# sensorTensao_rev5_5.net
KiCad netlist of a schematic drawn in EAGLE
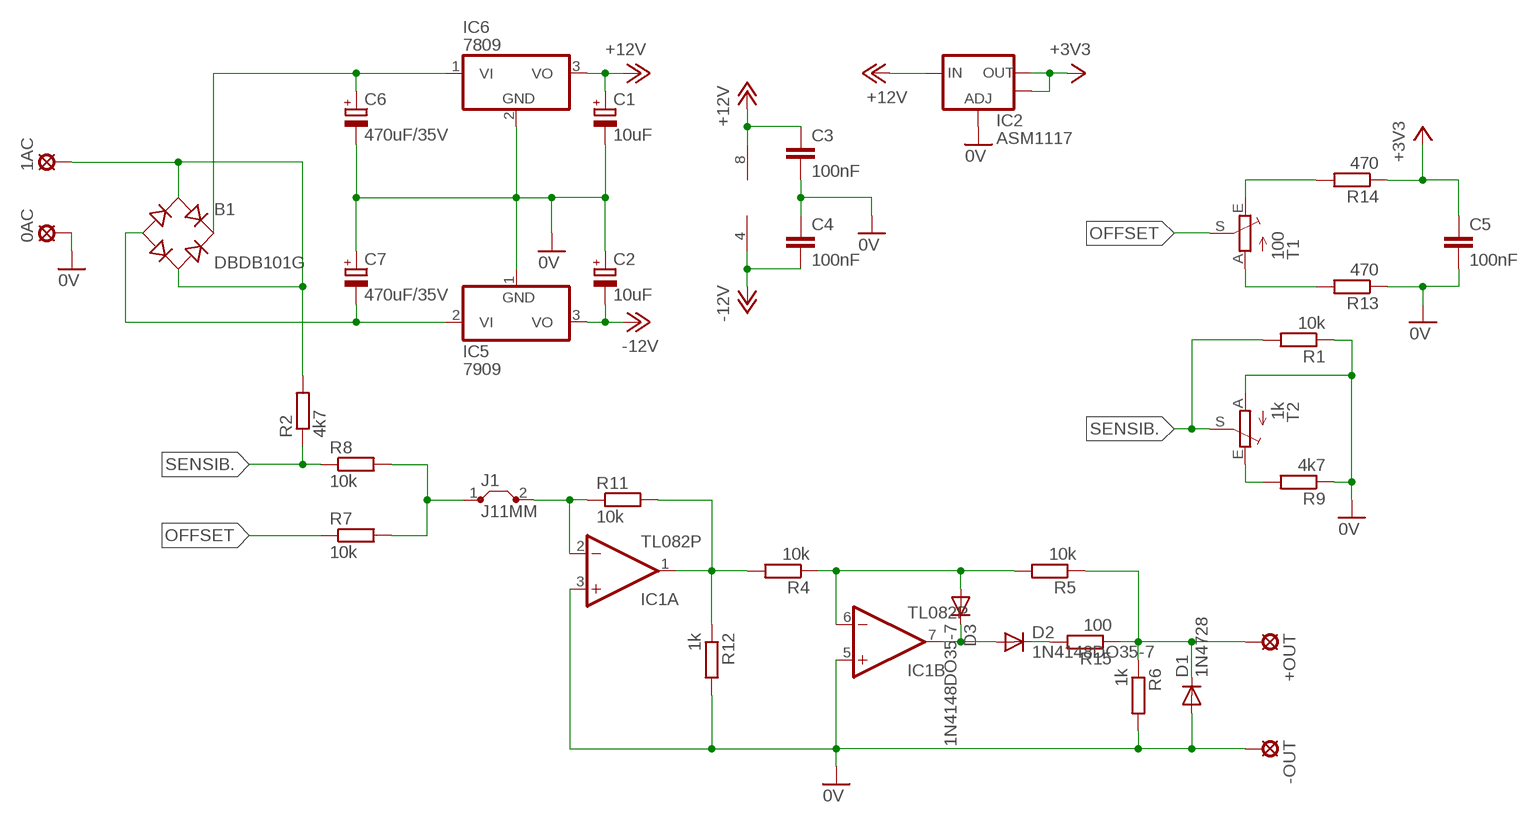
[diagram p0: schematic, sheet 1]

(export (version "E")
  (design (tool "Eeschema 10.0.6"))
  (components
    (comp (ref "+OUT")
      (value "+D")
      (footprint "eagle-import:LSP10")
      (libsource (lib "eagle-import") (part "LSP10"))
    )
    (comp (ref "-OUT")
      (value "0V")
      (footprint "eagle-import:LSP10")
      (libsource (lib "eagle-import") (part "LSP10"))
    )
    (comp (ref "0AC")
      (value "0V")
      (footprint "eagle-import:LSP10")
      (libsource (lib "eagle-import") (part "LSP10"))
    )
    (comp (ref "1AC")
      (value "AC")
      (footprint "eagle-import:LSP10")
      (libsource (lib "eagle-import") (part "LSP10"))
    )
    (comp (ref "B1")
      (value "DBDB101G")
      (footprint "eagle-import:DB")
      (libsource (lib "eagle-import") (part "DB?GDB101"))
    )
    (comp (ref "C1")
      (value "10uF")
      (footprint "eagle-import:E2,5-7")
      (libsource (lib "eagle-import") (part "CPOL-EUE2.5-7"))
    )
    (comp (ref "C2")
      (value "10uF")
      (footprint "eagle-import:E2,5-7")
      (libsource (lib "eagle-import") (part "CPOL-EUE2.5-7"))
    )
    (comp (ref "C3")
      (value "100nF")
      (footprint "eagle-import:C050-024X044")
      (libsource (lib "eagle-import") (part "C-EU050-024X044"))
    )
    (comp (ref "C4")
      (value "100nF")
      (footprint "eagle-import:C050-024X044")
      (libsource (lib "eagle-import") (part "C-EU050-024X044"))
    )
    (comp (ref "C5")
      (value "100nF")
      (footprint "eagle-import:C050-024X044")
      (libsource (lib "eagle-import") (part "C-EU050-024X044"))
    )
    (comp (ref "C6")
      (value "470uF/35V")
      (footprint "eagle-import:E3,5-10")
      (libsource (lib "eagle-import") (part "CPOL-EUE3.5-10"))
    )
    (comp (ref "C7")
      (value "470uF/35V")
      (footprint "eagle-import:E3,5-10")
      (libsource (lib "eagle-import") (part "CPOL-EUE3.5-10"))
    )
    (comp (ref "D1")
      (value "1N4728")
      (footprint "eagle-import:DO35-7")
      (libsource (lib "eagle-import") (part "1N4148DO35-7"))
    )
    (comp (ref "D2")
      (value "1N4148DO35-7")
      (footprint "eagle-import:DO35-7")
      (libsource (lib "eagle-import") (part "1N4148DO35-7"))
    )
    (comp (ref "D3")
      (value "1N4148DO35-7")
      (footprint "eagle-import:DO35-7")
      (libsource (lib "eagle-import") (part "1N4148DO35-7"))
    )
    (comp (ref "IC1")
      (value "TL082P")
      (footprint "eagle-import:DIL08")
      (libsource (lib "eagle-import") (part "TL082P"))
    )
    (comp (ref "IC2")
      (value "ASM1117")
      (footprint "eagle-import:SOT223")
      (libsource (lib "eagle-import") (part "V_REG_LM1117SOT223"))
    )
    (comp (ref "IC5")
      (value "7909")
      (footprint "eagle-import:TO220V")
      (libsource (lib "eagle-import") (part "7912"))
    )
    (comp (ref "IC6")
      (value "7809")
      (footprint "eagle-import:TO220V")
      (libsource (lib "eagle-import") (part "78TV12"))
    )
    (comp (ref "J1")
      (value "J11MM")
      (footprint "eagle-import:11")
      (libsource (lib "eagle-import") (part "J11MM"))
    )
    (comp (ref "R1")
      (value "10k")
      (footprint "eagle-import:0204_7")
      (libsource (lib "eagle-import") (part "R-EU_0204/7"))
    )
    (comp (ref "R2")
      (value "4k7")
      (footprint "eagle-import:0204_7")
      (libsource (lib "eagle-import") (part "R-EU_0204/7"))
    )
    (comp (ref "R4")
      (value "10k")
      (footprint "eagle-import:0204_7")
      (libsource (lib "eagle-import") (part "R-EU_0204/7"))
    )
    (comp (ref "R5")
      (value "10k")
      (footprint "eagle-import:0204_10")
      (libsource (lib "eagle-import") (part "R-EU_0204/10"))
    )
    (comp (ref "R6")
      (value "1k")
      (footprint "eagle-import:0204_7")
      (libsource (lib "eagle-import") (part "R-EU_0204/7"))
    )
    (comp (ref "R7")
      (value "10k")
      (footprint "eagle-import:0204_7")
      (libsource (lib "eagle-import") (part "R-EU_0204/7"))
    )
    (comp (ref "R8")
      (value "10k")
      (footprint "eagle-import:0204_7")
      (libsource (lib "eagle-import") (part "R-EU_0204/7"))
    )
    (comp (ref "R9")
      (value "4k7")
      (footprint "eagle-import:0204_7")
      (libsource (lib "eagle-import") (part "R-EU_0204/7"))
    )
    (comp (ref "R11")
      (value "10k")
      (footprint "eagle-import:0204_7")
      (libsource (lib "eagle-import") (part "R-EU_0204/7"))
    )
    (comp (ref "R12")
      (value "1k")
      (footprint "eagle-import:0204_7")
      (libsource (lib "eagle-import") (part "R-EU_0204/7"))
    )
    (comp (ref "R13")
      (value "470")
      (footprint "eagle-import:0204_7")
      (libsource (lib "eagle-import") (part "R-EU_0204/7"))
    )
    (comp (ref "R14")
      (value "470")
      (footprint "eagle-import:0204_7")
      (libsource (lib "eagle-import") (part "R-EU_0204/7"))
    )
    (comp (ref "R15")
      (value "100")
      (footprint "eagle-import:0204_7")
      (libsource (lib "eagle-import") (part "R-EU_0204/7"))
    )
    (comp (ref "T1")
      (value "100")
      (footprint "eagle-import:CA6V")
      (libsource (lib "eagle-import") (part "TRIM_EU-CA6V"))
    )
    (comp (ref "T2")
      (value "1k")
      (footprint "eagle-import:CA6V")
      (libsource (lib "eagle-import") (part "TRIM_EU-CA6V"))
    )
  )
  (nets
    (net (code "1") (name "+3V3") (class "Default")
      (node (ref "C5") (pin "1") (pinfunction "1_1") (pintype "passive"))
      (node (ref "IC2") (pin "2") (pinfunction "OUT_2") (pintype "output"))
      (node (ref "IC2") (pin "4") (pinfunction "OUT_4") (pintype "output"))
      (node (ref "R14") (pin "1") (pinfunction "1_1") (pintype "passive"))
    )
    (net (code "2") (name "+12V") (class "Default")
      (node (ref "C1") (pin "+") (pinfunction "+_+") (pintype "passive"))
      (node (ref "C3") (pin "1") (pinfunction "1_1") (pintype "passive"))
      (node (ref "IC1") (pin "8") (pinfunction "V+_8") (pintype "power_in"))
      (node (ref "IC2") (pin "3") (pinfunction "IN_3") (pintype "input"))
      (node (ref "IC6") (pin "3") (pinfunction "VO_3") (pintype "passive"))
    )
    (net (code "3") (name "-12V") (class "Default")
      (node (ref "C2") (pin "-") (pinfunction "-_-") (pintype "passive"))
      (node (ref "C4") (pin "2") (pinfunction "2_2") (pintype "passive"))
      (node (ref "IC1") (pin "4") (pinfunction "V-_4") (pintype "power_in"))
      (node (ref "IC5") (pin "3") (pinfunction "VO_3") (pintype "passive"))
    )
    (net (code "4") (name "0V") (class "Default")
      (node (ref "-OUT") (pin "MP") (pinfunction "MP_MP") (pintype "passive"))
      (node (ref "0AC") (pin "MP") (pinfunction "MP_MP") (pintype "passive"))
      (node (ref "C1") (pin "-") (pinfunction "-_-") (pintype "passive"))
      (node (ref "C2") (pin "+") (pinfunction "+_+") (pintype "passive"))
      (node (ref "C3") (pin "2") (pinfunction "2_2") (pintype "passive"))
      (node (ref "C4") (pin "1") (pinfunction "1_1") (pintype "passive"))
      (node (ref "C5") (pin "2") (pinfunction "2_2") (pintype "passive"))
      (node (ref "C6") (pin "-") (pinfunction "-_-") (pintype "passive"))
      (node (ref "C7") (pin "+") (pinfunction "+_+") (pintype "passive"))
      (node (ref "D1") (pin "A") (pinfunction "A_A") (pintype "passive"))
      (node (ref "IC1") (pin "3") (pinfunction "+IN_3") (pintype "input"))
      (node (ref "IC1") (pin "5") (pinfunction "+IN_5") (pintype "input"))
      (node (ref "IC2") (pin "1") (pinfunction "ADJ_1") (pintype "input"))
      (node (ref "IC5") (pin "1") (pinfunction "GND_1") (pintype "passive"))
      (node (ref "IC6") (pin "2") (pinfunction "GND_2") (pintype "passive"))
      (node (ref "R1") (pin "1") (pinfunction "1_1") (pintype "passive"))
      (node (ref "R12") (pin "2") (pinfunction "2_2") (pintype "passive"))
      (node (ref "R13") (pin "1") (pinfunction "1_1") (pintype "passive"))
      (node (ref "R6") (pin "2") (pinfunction "2_2") (pintype "passive"))
      (node (ref "R9") (pin "1") (pinfunction "1_1") (pintype "passive"))
      (node (ref "T2") (pin "A") (pinfunction "A_A") (pintype "passive"))
    )
    (net (code "5") (name "Net-(+OUT-PadMP)") (class "Default")
      (node (ref "+OUT") (pin "MP") (pinfunction "MP_MP") (pintype "passive"))
      (node (ref "D1") (pin "C") (pinfunction "C_C") (pintype "passive"))
      (node (ref "R15") (pin "1") (pinfunction "1_1") (pintype "passive"))
      (node (ref "R5") (pin "1") (pinfunction "1_1") (pintype "passive"))
      (node (ref "R6") (pin "1") (pinfunction "1_1") (pintype "passive"))
    )
    (net (code "6") (name "Net-(1AC-PadMP)") (class "Default")
      (node (ref "1AC") (pin "MP") (pinfunction "MP_MP") (pintype "passive"))
      (node (ref "B1") (pin "AC1") (pinfunction "AC1_AC1") (pintype "passive"))
      (node (ref "B1") (pin "AC2") (pinfunction "AC2_AC2") (pintype "passive"))
      (node (ref "R2") (pin "2") (pinfunction "2_2") (pintype "passive"))
    )
    (net (code "7") (name "Net-(D2-PadC)") (class "Default")
      (node (ref "D2") (pin "C") (pinfunction "C_C") (pintype "passive"))
      (node (ref "R15") (pin "2") (pinfunction "2_2") (pintype "passive"))
    )
    (net (code "8") (name "Net-(IC1A--IN)") (class "Default")
      (node (ref "IC1") (pin "2") (pinfunction "-IN_2") (pintype "input"))
      (node (ref "J1") (pin "2") (pinfunction "2_2") (pintype "passive"))
      (node (ref "R11") (pin "1") (pinfunction "1_1") (pintype "passive"))
    )
    (net (code "9") (name "Net-(IC1A-OUT)") (class "Default")
      (node (ref "IC1") (pin "1") (pinfunction "OUT_1") (pintype "output"))
      (node (ref "R11") (pin "2") (pinfunction "2_2") (pintype "passive"))
      (node (ref "R12") (pin "1") (pinfunction "1_1") (pintype "passive"))
      (node (ref "R4") (pin "2") (pinfunction "2_2") (pintype "passive"))
    )
    (net (code "10") (name "Net-(IC1B--IN)") (class "Default")
      (node (ref "D3") (pin "A") (pinfunction "A_A") (pintype "passive"))
      (node (ref "IC1") (pin "6") (pinfunction "-IN_6") (pintype "input"))
      (node (ref "R4") (pin "1") (pinfunction "1_1") (pintype "passive"))
      (node (ref "R5") (pin "2") (pinfunction "2_2") (pintype "passive"))
    )
    (net (code "11") (name "Net-(IC1B-OUT)") (class "Default")
      (node (ref "D2") (pin "A") (pinfunction "A_A") (pintype "passive"))
      (node (ref "D3") (pin "C") (pinfunction "C_C") (pintype "passive"))
      (node (ref "IC1") (pin "7") (pinfunction "OUT_7") (pintype "output"))
    )
    (net (code "12") (name "Net-(IC5-VI)") (class "Default")
      (node (ref "B1") (pin "-") (pinfunction "-_-") (pintype "passive"))
      (node (ref "C7") (pin "-") (pinfunction "-_-") (pintype "passive"))
      (node (ref "IC5") (pin "2") (pinfunction "VI_2") (pintype "input"))
    )
    (net (code "13") (name "Net-(IC6-VI)") (class "Default")
      (node (ref "B1") (pin "+") (pinfunction "+_+") (pintype "passive"))
      (node (ref "C6") (pin "+") (pinfunction "+_+") (pintype "passive"))
      (node (ref "IC6") (pin "1") (pinfunction "VI_1") (pintype "input"))
    )
    (net (code "14") (name "Net-(J1-Pad1)") (class "Default")
      (node (ref "J1") (pin "1") (pinfunction "1_1") (pintype "passive"))
      (node (ref "R7") (pin "2") (pinfunction "2_2") (pintype "passive"))
      (node (ref "R8") (pin "2") (pinfunction "2_2") (pintype "passive"))
    )
    (net (code "15") (name "Net-(R9-Pad2)") (class "Default")
      (node (ref "R9") (pin "2") (pinfunction "2_2") (pintype "passive"))
      (node (ref "T2") (pin "E") (pinfunction "E_E") (pintype "passive"))
    )
    (net (code "16") (name "Net-(R13-Pad2)") (class "Default")
      (node (ref "R13") (pin "2") (pinfunction "2_2") (pintype "passive"))
      (node (ref "T1") (pin "A") (pinfunction "A_A") (pintype "passive"))
    )
    (net (code "17") (name "Net-(R14-Pad2)") (class "Default")
      (node (ref "R14") (pin "2") (pinfunction "2_2") (pintype "passive"))
      (node (ref "T1") (pin "E") (pinfunction "E_E") (pintype "passive"))
    )
    (net (code "18") (name "OFFSET") (class "Default")
      (node (ref "R7") (pin "1") (pinfunction "1_1") (pintype "passive"))
      (node (ref "T1") (pin "S") (pinfunction "S_S") (pintype "passive"))
    )
    (net (code "19") (name "SENSIB.") (class "Default")
      (node (ref "R1") (pin "2") (pinfunction "2_2") (pintype "passive"))
      (node (ref "R2") (pin "1") (pinfunction "1_1") (pintype "passive"))
      (node (ref "R8") (pin "1") (pinfunction "1_1") (pintype "passive"))
      (node (ref "T2") (pin "S") (pinfunction "S_S") (pintype "passive"))
    )
  )
)
